# schematic-single-motor.net
KiCad netlist of a schematic drawn in EAGLE
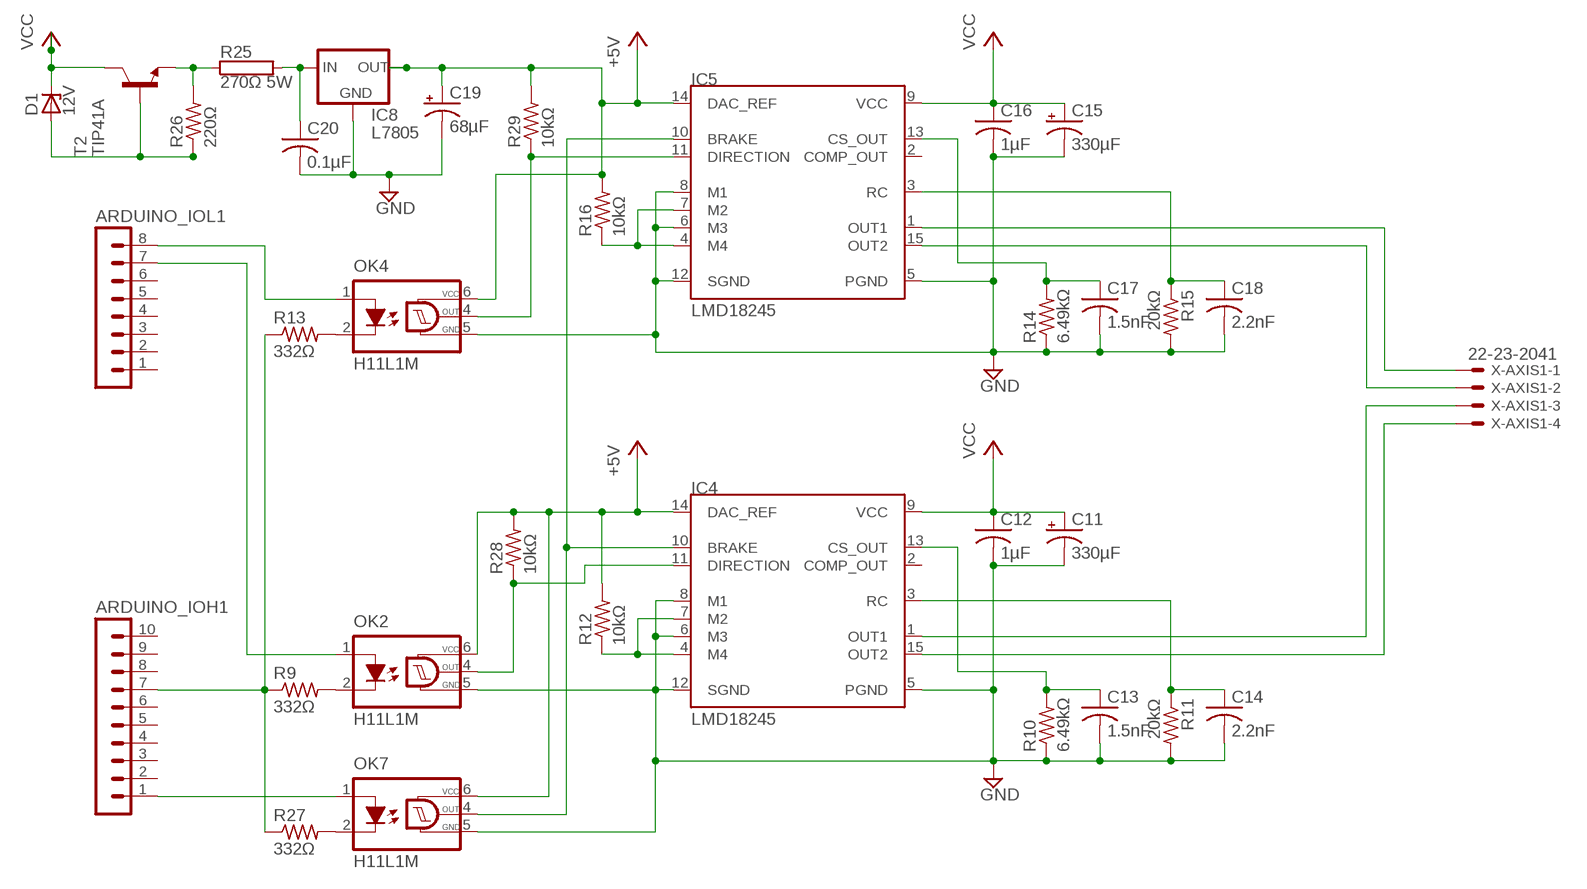
[diagram p0: schematic, sheet 1]

(export (version "E")
  (design (tool "Eeschema 10.0.6"))
  (components
    (comp (ref "ARDUINO_IOH1")
      (value "MA10-1")
      (footprint "eagle-import:MA10-1")
      (libsource (lib "eagle-import") (part "MA10-1"))
    )
    (comp (ref "ARDUINO_IOL1")
      (value "MA08-1")
      (footprint "eagle-import:MA08-1")
      (libsource (lib "eagle-import") (part "MA08-1"))
    )
    (comp (ref "C11")
      (value "330µF")
      (footprint "eagle-import:E5-13")
      (libsource (lib "eagle-import") (part "CPOL-USE5-13"))
    )
    (comp (ref "C12")
      (value "1µF")
      (footprint "eagle-import:C050-024X044")
      (libsource (lib "eagle-import") (part "C-US050-024X044"))
    )
    (comp (ref "C13")
      (value "1.5nF")
      (footprint "eagle-import:C050-024X044")
      (libsource (lib "eagle-import") (part "C-US050-024X044"))
    )
    (comp (ref "C14")
      (value "2.2nF")
      (footprint "eagle-import:C050-024X044")
      (libsource (lib "eagle-import") (part "C-US050-024X044"))
    )
    (comp (ref "C15")
      (value "330µF")
      (footprint "eagle-import:E5-13")
      (libsource (lib "eagle-import") (part "CPOL-USE5-13"))
    )
    (comp (ref "C16")
      (value "1µF")
      (footprint "eagle-import:C050-024X044")
      (libsource (lib "eagle-import") (part "C-US050-024X044"))
    )
    (comp (ref "C17")
      (value "1.5nF")
      (footprint "eagle-import:C050-024X044")
      (libsource (lib "eagle-import") (part "C-US050-024X044"))
    )
    (comp (ref "C18")
      (value "2.2nF")
      (footprint "eagle-import:C050-024X044")
      (libsource (lib "eagle-import") (part "C-US050-024X044"))
    )
    (comp (ref "C19")
      (value "68µF")
      (footprint "eagle-import:E2,5-6")
      (libsource (lib "eagle-import") (part "CPOL-USE2.5-6"))
    )
    (comp (ref "C20")
      (value "0.1µF")
      (footprint "eagle-import:C102-054X133")
      (libsource (lib "eagle-import") (part "C-US102-054X133"))
    )
    (comp (ref "D1")
      (value "12V")
      (footprint "eagle-import:DO41Z10")
      (libsource (lib "eagle-import") (part "ZPY"))
    )
    (comp (ref "IC4")
      (value "LMD18245")
      (footprint "eagle-import:MULTIWATT-15")
      (fields (field (name "MF") "Texas Instruments"))
      (libsource (lib "eagle-import") (part "LMD18245"))
    )
    (comp (ref "IC5")
      (value "LMD18245")
      (footprint "eagle-import:MULTIWATT-15")
      (fields (field (name "MF") "Texas Instruments"))
      (libsource (lib "eagle-import") (part "LMD18245"))
    )
    (comp (ref "IC8")
      (value "L7805")
      (footprint "eagle-import:78XXS")
      (libsource (lib "eagle-import") (part "78XXS"))
    )
    (comp (ref "OK2")
      (value "H11L1M")
      (footprint "eagle-import:DIL06")
      (fields (field (name "MF") "FAIRCHILD SEMICONDUCTOR") (field (name "MPN") "H11L1-M"))
      (libsource (lib "eagle-import") (part "H11LM1"))
    )
    (comp (ref "OK4")
      (value "H11L1M")
      (footprint "eagle-import:DIL06")
      (fields (field (name "MF") "FAIRCHILD SEMICONDUCTOR") (field (name "MPN") "H11L1-M"))
      (libsource (lib "eagle-import") (part "H11LM1"))
    )
    (comp (ref "OK7")
      (value "H11L1M")
      (footprint "eagle-import:DIL06")
      (fields (field (name "MF") "FAIRCHILD SEMICONDUCTOR") (field (name "MPN") "H11L1-M"))
      (libsource (lib "eagle-import") (part "H11LM1"))
    )
    (comp (ref "R9")
      (value "332Ω")
      (footprint "eagle-import:0204_7")
      (libsource (lib "eagle-import") (part "R-US_0204/7"))
    )
    (comp (ref "R10")
      (value "6.49kΩ")
      (footprint "eagle-import:0204_7")
      (libsource (lib "eagle-import") (part "R-US_0204/7"))
    )
    (comp (ref "R11")
      (value "20kΩ")
      (footprint "eagle-import:0204_7")
      (libsource (lib "eagle-import") (part "R-US_0204/7"))
    )
    (comp (ref "R12")
      (value "10kΩ")
      (footprint "eagle-import:0204_7")
      (libsource (lib "eagle-import") (part "R-US_0204/7"))
    )
    (comp (ref "R13")
      (value "332Ω")
      (footprint "eagle-import:0204_7")
      (libsource (lib "eagle-import") (part "R-US_0204/7"))
    )
    (comp (ref "R14")
      (value "6.49kΩ")
      (footprint "eagle-import:0204_7")
      (libsource (lib "eagle-import") (part "R-US_0204/7"))
    )
    (comp (ref "R15")
      (value "20kΩ")
      (footprint "eagle-import:0204_7")
      (libsource (lib "eagle-import") (part "R-US_0204/7"))
    )
    (comp (ref "R16")
      (value "10kΩ")
      (footprint "eagle-import:0204_7")
      (libsource (lib "eagle-import") (part "R-US_0204/7"))
    )
    (comp (ref "R25")
      (value "270Ω 5W")
      (footprint "eagle-import:HPS523")
      (libsource (lib "eagle-import") (part "RHPS523"))
    )
    (comp (ref "R26")
      (value "220Ω")
      (footprint "eagle-import:0204_7")
      (libsource (lib "eagle-import") (part "R-US_0204/7"))
    )
    (comp (ref "R27")
      (value "332Ω")
      (footprint "eagle-import:0204_7")
      (libsource (lib "eagle-import") (part "R-US_0204/7"))
    )
    (comp (ref "R28")
      (value "10kΩ")
      (footprint "eagle-import:0204_7")
      (libsource (lib "eagle-import") (part "R-US_0204/7"))
    )
    (comp (ref "R29")
      (value "10kΩ")
      (footprint "eagle-import:0204_7")
      (libsource (lib "eagle-import") (part "R-US_0204/7"))
    )
    (comp (ref "T2")
      (value "TIP41A")
      (footprint "eagle-import:TO202V")
      (libsource (lib "eagle-import") (part "-NPN-TO202V"))
    )
    (comp (ref "X-AXIS1")
      (value "22-23-2041")
      (footprint "eagle-import:22-23-2041")
      (fields (field (name "MF") "MOLEX"))
      (libsource (lib "eagle-import") (part "22-23-2041"))
    )
  )
  (nets
    (net (code "1") (name "+5V") (class "Default")
      (node (ref "C19") (pin "+") (pinfunction "+_+") (pintype "passive"))
      (node (ref "IC4") (pin "14") (pinfunction "DAC_REF_14") (pintype "power_in"))
      (node (ref "IC5") (pin "14") (pinfunction "DAC_REF_14") (pintype "power_in"))
      (node (ref "IC8") (pin "OUT") (pinfunction "OUT_OUT") (pintype "passive"))
      (node (ref "OK2") (pin "6") (pinfunction "VCC_6") (pintype "power_in"))
      (node (ref "OK4") (pin "6") (pinfunction "VCC_6") (pintype "power_in"))
      (node (ref "OK7") (pin "6") (pinfunction "VCC_6") (pintype "power_in"))
      (node (ref "R12") (pin "2") (pinfunction "2_2") (pintype "passive"))
      (node (ref "R16") (pin "2") (pinfunction "2_2") (pintype "passive"))
      (node (ref "R28") (pin "2") (pinfunction "2_2") (pintype "passive"))
      (node (ref "R29") (pin "2") (pinfunction "2_2") (pintype "passive"))
    )
    (net (code "2") (name "GND") (class "Default")
      (node (ref "C11") (pin "-") (pinfunction "-_-") (pintype "passive"))
      (node (ref "C12") (pin "2") (pinfunction "2_2") (pintype "passive"))
      (node (ref "C13") (pin "2") (pinfunction "2_2") (pintype "passive"))
      (node (ref "C14") (pin "2") (pinfunction "2_2") (pintype "passive"))
      (node (ref "C15") (pin "-") (pinfunction "-_-") (pintype "passive"))
      (node (ref "C16") (pin "2") (pinfunction "2_2") (pintype "passive"))
      (node (ref "C17") (pin "2") (pinfunction "2_2") (pintype "passive"))
      (node (ref "C18") (pin "2") (pinfunction "2_2") (pintype "passive"))
      (node (ref "C19") (pin "-") (pinfunction "-_-") (pintype "passive"))
      (node (ref "C20") (pin "2") (pinfunction "2_2") (pintype "passive"))
      (node (ref "IC4") (pin "12") (pinfunction "SGND_12") (pintype "power_in"))
      (node (ref "IC4") (pin "5") (pinfunction "PGND_5") (pintype "power_in"))
      (node (ref "IC4") (pin "6") (pinfunction "M3_6") (pintype "input"))
      (node (ref "IC4") (pin "8") (pinfunction "M1_8") (pintype "input"))
      (node (ref "IC5") (pin "12") (pinfunction "SGND_12") (pintype "power_in"))
      (node (ref "IC5") (pin "5") (pinfunction "PGND_5") (pintype "power_in"))
      (node (ref "IC5") (pin "6") (pinfunction "M3_6") (pintype "input"))
      (node (ref "IC5") (pin "8") (pinfunction "M1_8") (pintype "input"))
      (node (ref "IC8") (pin "GND") (pinfunction "GND_GND") (pintype "input"))
      (node (ref "OK2") (pin "5") (pinfunction "GND_5") (pintype "power_in"))
      (node (ref "OK4") (pin "5") (pinfunction "GND_5") (pintype "power_in"))
      (node (ref "OK7") (pin "5") (pinfunction "GND_5") (pintype "power_in"))
      (node (ref "R10") (pin "1") (pinfunction "1_1") (pintype "passive"))
      (node (ref "R11") (pin "2") (pinfunction "2_2") (pintype "passive"))
      (node (ref "R14") (pin "1") (pinfunction "1_1") (pintype "passive"))
      (node (ref "R15") (pin "2") (pinfunction "2_2") (pintype "passive"))
    )
    (net (code "3") (name "Net-(ARDUINO_IOH1-Pad7)") (class "Default")
      (node (ref "ARDUINO_IOH1") (pin "7") (pinfunction "7_7") (pintype "passive"))
      (node (ref "R13") (pin "1") (pinfunction "1_1") (pintype "passive"))
      (node (ref "R27") (pin "1") (pinfunction "1_1") (pintype "passive"))
      (node (ref "R9") (pin "1") (pinfunction "1_1") (pintype "passive"))
    )
    (net (code "4") (name "Net-(C20-Pad1)") (class "Default")
      (node (ref "C20") (pin "1") (pinfunction "1_1") (pintype "passive"))
      (node (ref "IC8") (pin "IN") (pinfunction "IN_IN") (pintype "input"))
      (node (ref "R25") (pin "2") (pinfunction "2_2") (pintype "passive"))
    )
    (net (code "5") (name "Net-(IC4-BRAKE)") (class "Default")
      (node (ref "IC4") (pin "10") (pinfunction "BRAKE_10") (pintype "input"))
      (node (ref "IC5") (pin "10") (pinfunction "BRAKE_10") (pintype "input"))
      (node (ref "OK7") (pin "4") (pinfunction "OUT_4") (pintype "output"))
    )
    (net (code "6") (name "Net-(IC4-CS_OUT)") (class "Default")
      (node (ref "C13") (pin "1") (pinfunction "1_1") (pintype "passive"))
      (node (ref "IC4") (pin "13") (pinfunction "CS_OUT_13") (pintype "output"))
      (node (ref "R10") (pin "2") (pinfunction "2_2") (pintype "passive"))
    )
    (net (code "7") (name "Net-(IC4-DIRECTION)") (class "Default")
      (node (ref "IC4") (pin "11") (pinfunction "DIRECTION_11") (pintype "input"))
      (node (ref "OK2") (pin "4") (pinfunction "OUT_4") (pintype "output"))
      (node (ref "R28") (pin "1") (pinfunction "1_1") (pintype "passive"))
    )
    (net (code "8") (name "Net-(IC4-M2)") (class "Default")
      (node (ref "IC4") (pin "4") (pinfunction "M4_4") (pintype "input"))
      (node (ref "IC4") (pin "7") (pinfunction "M2_7") (pintype "input"))
      (node (ref "R12") (pin "1") (pinfunction "1_1") (pintype "passive"))
    )
    (net (code "9") (name "Net-(IC4-OUT1)") (class "Default")
      (node (ref "IC4") (pin "1") (pinfunction "OUT1_1") (pintype "output"))
      (node (ref "X-AXIS1") (pin "3") (pinfunction "S_3") (pintype "passive"))
    )
    (net (code "10") (name "Net-(IC4-OUT2)") (class "Default")
      (node (ref "IC4") (pin "15") (pinfunction "OUT2_15") (pintype "output"))
      (node (ref "X-AXIS1") (pin "4") (pinfunction "S_4") (pintype "passive"))
    )
    (net (code "11") (name "Net-(IC4-RC)") (class "Default")
      (node (ref "C14") (pin "1") (pinfunction "1_1") (pintype "passive"))
      (node (ref "IC4") (pin "3") (pinfunction "RC_3") (pintype "passive"))
      (node (ref "R11") (pin "1") (pinfunction "1_1") (pintype "passive"))
    )
    (net (code "12") (name "Net-(IC5-CS_OUT)") (class "Default")
      (node (ref "C17") (pin "1") (pinfunction "1_1") (pintype "passive"))
      (node (ref "IC5") (pin "13") (pinfunction "CS_OUT_13") (pintype "output"))
      (node (ref "R14") (pin "2") (pinfunction "2_2") (pintype "passive"))
    )
    (net (code "13") (name "Net-(IC5-DIRECTION)") (class "Default")
      (node (ref "IC5") (pin "11") (pinfunction "DIRECTION_11") (pintype "input"))
      (node (ref "OK4") (pin "4") (pinfunction "OUT_4") (pintype "output"))
      (node (ref "R29") (pin "1") (pinfunction "1_1") (pintype "passive"))
    )
    (net (code "14") (name "Net-(IC5-M2)") (class "Default")
      (node (ref "IC5") (pin "4") (pinfunction "M4_4") (pintype "input"))
      (node (ref "IC5") (pin "7") (pinfunction "M2_7") (pintype "input"))
      (node (ref "R16") (pin "1") (pinfunction "1_1") (pintype "passive"))
    )
    (net (code "15") (name "Net-(IC5-OUT1)") (class "Default")
      (node (ref "IC5") (pin "1") (pinfunction "OUT1_1") (pintype "output"))
      (node (ref "X-AXIS1") (pin "1") (pinfunction "S_1") (pintype "passive"))
    )
    (net (code "16") (name "Net-(IC5-OUT2)") (class "Default")
      (node (ref "IC5") (pin "15") (pinfunction "OUT2_15") (pintype "output"))
      (node (ref "X-AXIS1") (pin "2") (pinfunction "S_2") (pintype "passive"))
    )
    (net (code "17") (name "Net-(IC5-RC)") (class "Default")
      (node (ref "C18") (pin "1") (pinfunction "1_1") (pintype "passive"))
      (node (ref "IC5") (pin "3") (pinfunction "RC_3") (pintype "passive"))
      (node (ref "R15") (pin "1") (pinfunction "1_1") (pintype "passive"))
    )
    (net (code "18") (name "Net-(OK2-A)") (class "Default")
      (node (ref "ARDUINO_IOL1") (pin "7") (pinfunction "7_7") (pintype "passive"))
      (node (ref "OK2") (pin "1") (pinfunction "A_1") (pintype "passive"))
    )
    (net (code "19") (name "Net-(OK2-C)") (class "Default")
      (node (ref "OK2") (pin "2") (pinfunction "C_2") (pintype "passive"))
      (node (ref "R9") (pin "2") (pinfunction "2_2") (pintype "passive"))
    )
    (net (code "20") (name "Net-(OK4-A)") (class "Default")
      (node (ref "ARDUINO_IOL1") (pin "8") (pinfunction "8_8") (pintype "passive"))
      (node (ref "OK4") (pin "1") (pinfunction "A_1") (pintype "passive"))
    )
    (net (code "21") (name "Net-(OK4-C)") (class "Default")
      (node (ref "OK4") (pin "2") (pinfunction "C_2") (pintype "passive"))
      (node (ref "R13") (pin "2") (pinfunction "2_2") (pintype "passive"))
    )
    (net (code "22") (name "Net-(OK7-A)") (class "Default")
      (node (ref "ARDUINO_IOH1") (pin "1") (pinfunction "1_1") (pintype "passive"))
      (node (ref "OK7") (pin "1") (pinfunction "A_1") (pintype "passive"))
    )
    (net (code "23") (name "Net-(OK7-C)") (class "Default")
      (node (ref "OK7") (pin "2") (pinfunction "C_2") (pintype "passive"))
      (node (ref "R27") (pin "2") (pinfunction "2_2") (pintype "passive"))
    )
    (net (code "24") (name "Net-(T2-B)") (class "Default")
      (node (ref "D1") (pin "A") (pinfunction "A_A") (pintype "passive"))
      (node (ref "R26") (pin "1") (pinfunction "1_1") (pintype "passive"))
      (node (ref "T2") (pin "3") (pinfunction "B_3") (pintype "passive"))
    )
    (net (code "25") (name "Net-(T2-E)") (class "Default")
      (node (ref "R25") (pin "1") (pinfunction "1_1") (pintype "passive"))
      (node (ref "R26") (pin "2") (pinfunction "2_2") (pintype "passive"))
      (node (ref "T2") (pin "1") (pinfunction "E_1") (pintype "passive"))
    )
    (net (code "26") (name "VCC") (class "Default")
      (node (ref "C11") (pin "+") (pinfunction "+_+") (pintype "passive"))
      (node (ref "C12") (pin "1") (pinfunction "1_1") (pintype "passive"))
      (node (ref "C15") (pin "+") (pinfunction "+_+") (pintype "passive"))
      (node (ref "C16") (pin "1") (pinfunction "1_1") (pintype "passive"))
      (node (ref "D1") (pin "C") (pinfunction "C_C") (pintype "passive"))
      (node (ref "IC4") (pin "9") (pinfunction "VCC_9") (pintype "power_in"))
      (node (ref "IC5") (pin "9") (pinfunction "VCC_9") (pintype "power_in"))
      (node (ref "T2") (pin "2") (pinfunction "C_2") (pintype "passive"))
    )
    (net (code "27") (name "unconnected-(ARDUINO_IOH1-Pad2)") (class "Default")
      (node (ref "ARDUINO_IOH1") (pin "2") (pinfunction "2_2") (pintype "passive"))
    )
    (net (code "28") (name "unconnected-(ARDUINO_IOH1-Pad3)") (class "Default")
      (node (ref "ARDUINO_IOH1") (pin "3") (pinfunction "3_3") (pintype "passive"))
    )
    (net (code "29") (name "unconnected-(ARDUINO_IOH1-Pad4)") (class "Default")
      (node (ref "ARDUINO_IOH1") (pin "4") (pinfunction "4_4") (pintype "passive"))
    )
    (net (code "30") (name "unconnected-(ARDUINO_IOH1-Pad5)") (class "Default")
      (node (ref "ARDUINO_IOH1") (pin "5") (pinfunction "5_5") (pintype "passive"))
    )
    (net (code "31") (name "unconnected-(ARDUINO_IOH1-Pad6)") (class "Default")
      (node (ref "ARDUINO_IOH1") (pin "6") (pinfunction "6_6") (pintype "passive"))
    )
    (net (code "32") (name "unconnected-(ARDUINO_IOH1-Pad8)") (class "Default")
      (node (ref "ARDUINO_IOH1") (pin "8") (pinfunction "8_8") (pintype "passive"))
    )
    (net (code "33") (name "unconnected-(ARDUINO_IOH1-Pad9)") (class "Default")
      (node (ref "ARDUINO_IOH1") (pin "9") (pinfunction "9_9") (pintype "passive"))
    )
    (net (code "34") (name "unconnected-(ARDUINO_IOH1-Pad10)") (class "Default")
      (node (ref "ARDUINO_IOH1") (pin "10") (pinfunction "10_10") (pintype "passive"))
    )
    (net (code "35") (name "unconnected-(ARDUINO_IOL1-Pad1)") (class "Default")
      (node (ref "ARDUINO_IOL1") (pin "1") (pinfunction "1_1") (pintype "passive"))
    )
    (net (code "36") (name "unconnected-(ARDUINO_IOL1-Pad2)") (class "Default")
      (node (ref "ARDUINO_IOL1") (pin "2") (pinfunction "2_2") (pintype "passive"))
    )
    (net (code "37") (name "unconnected-(ARDUINO_IOL1-Pad3)") (class "Default")
      (node (ref "ARDUINO_IOL1") (pin "3") (pinfunction "3_3") (pintype "passive"))
    )
    (net (code "38") (name "unconnected-(ARDUINO_IOL1-Pad4)") (class "Default")
      (node (ref "ARDUINO_IOL1") (pin "4") (pinfunction "4_4") (pintype "passive"))
    )
    (net (code "39") (name "unconnected-(ARDUINO_IOL1-Pad5)") (class "Default")
      (node (ref "ARDUINO_IOL1") (pin "5") (pinfunction "5_5") (pintype "passive"))
    )
    (net (code "40") (name "unconnected-(ARDUINO_IOL1-Pad6)") (class "Default")
      (node (ref "ARDUINO_IOL1") (pin "6") (pinfunction "6_6") (pintype "passive"))
    )
    (net (code "41") (name "unconnected-(IC4-COMP_OUT-Pad2)") (class "Default")
      (node (ref "IC4") (pin "2") (pinfunction "COMP_OUT_2") (pintype "output"))
    )
    (net (code "42") (name "unconnected-(IC5-COMP_OUT-Pad2)") (class "Default")
      (node (ref "IC5") (pin "2") (pinfunction "COMP_OUT_2") (pintype "output"))
    )
  )
)
